# Schaltplan_Vier-Gewinnt_V3.net
KiCad netlist of a schematic drawn in EasyEDA
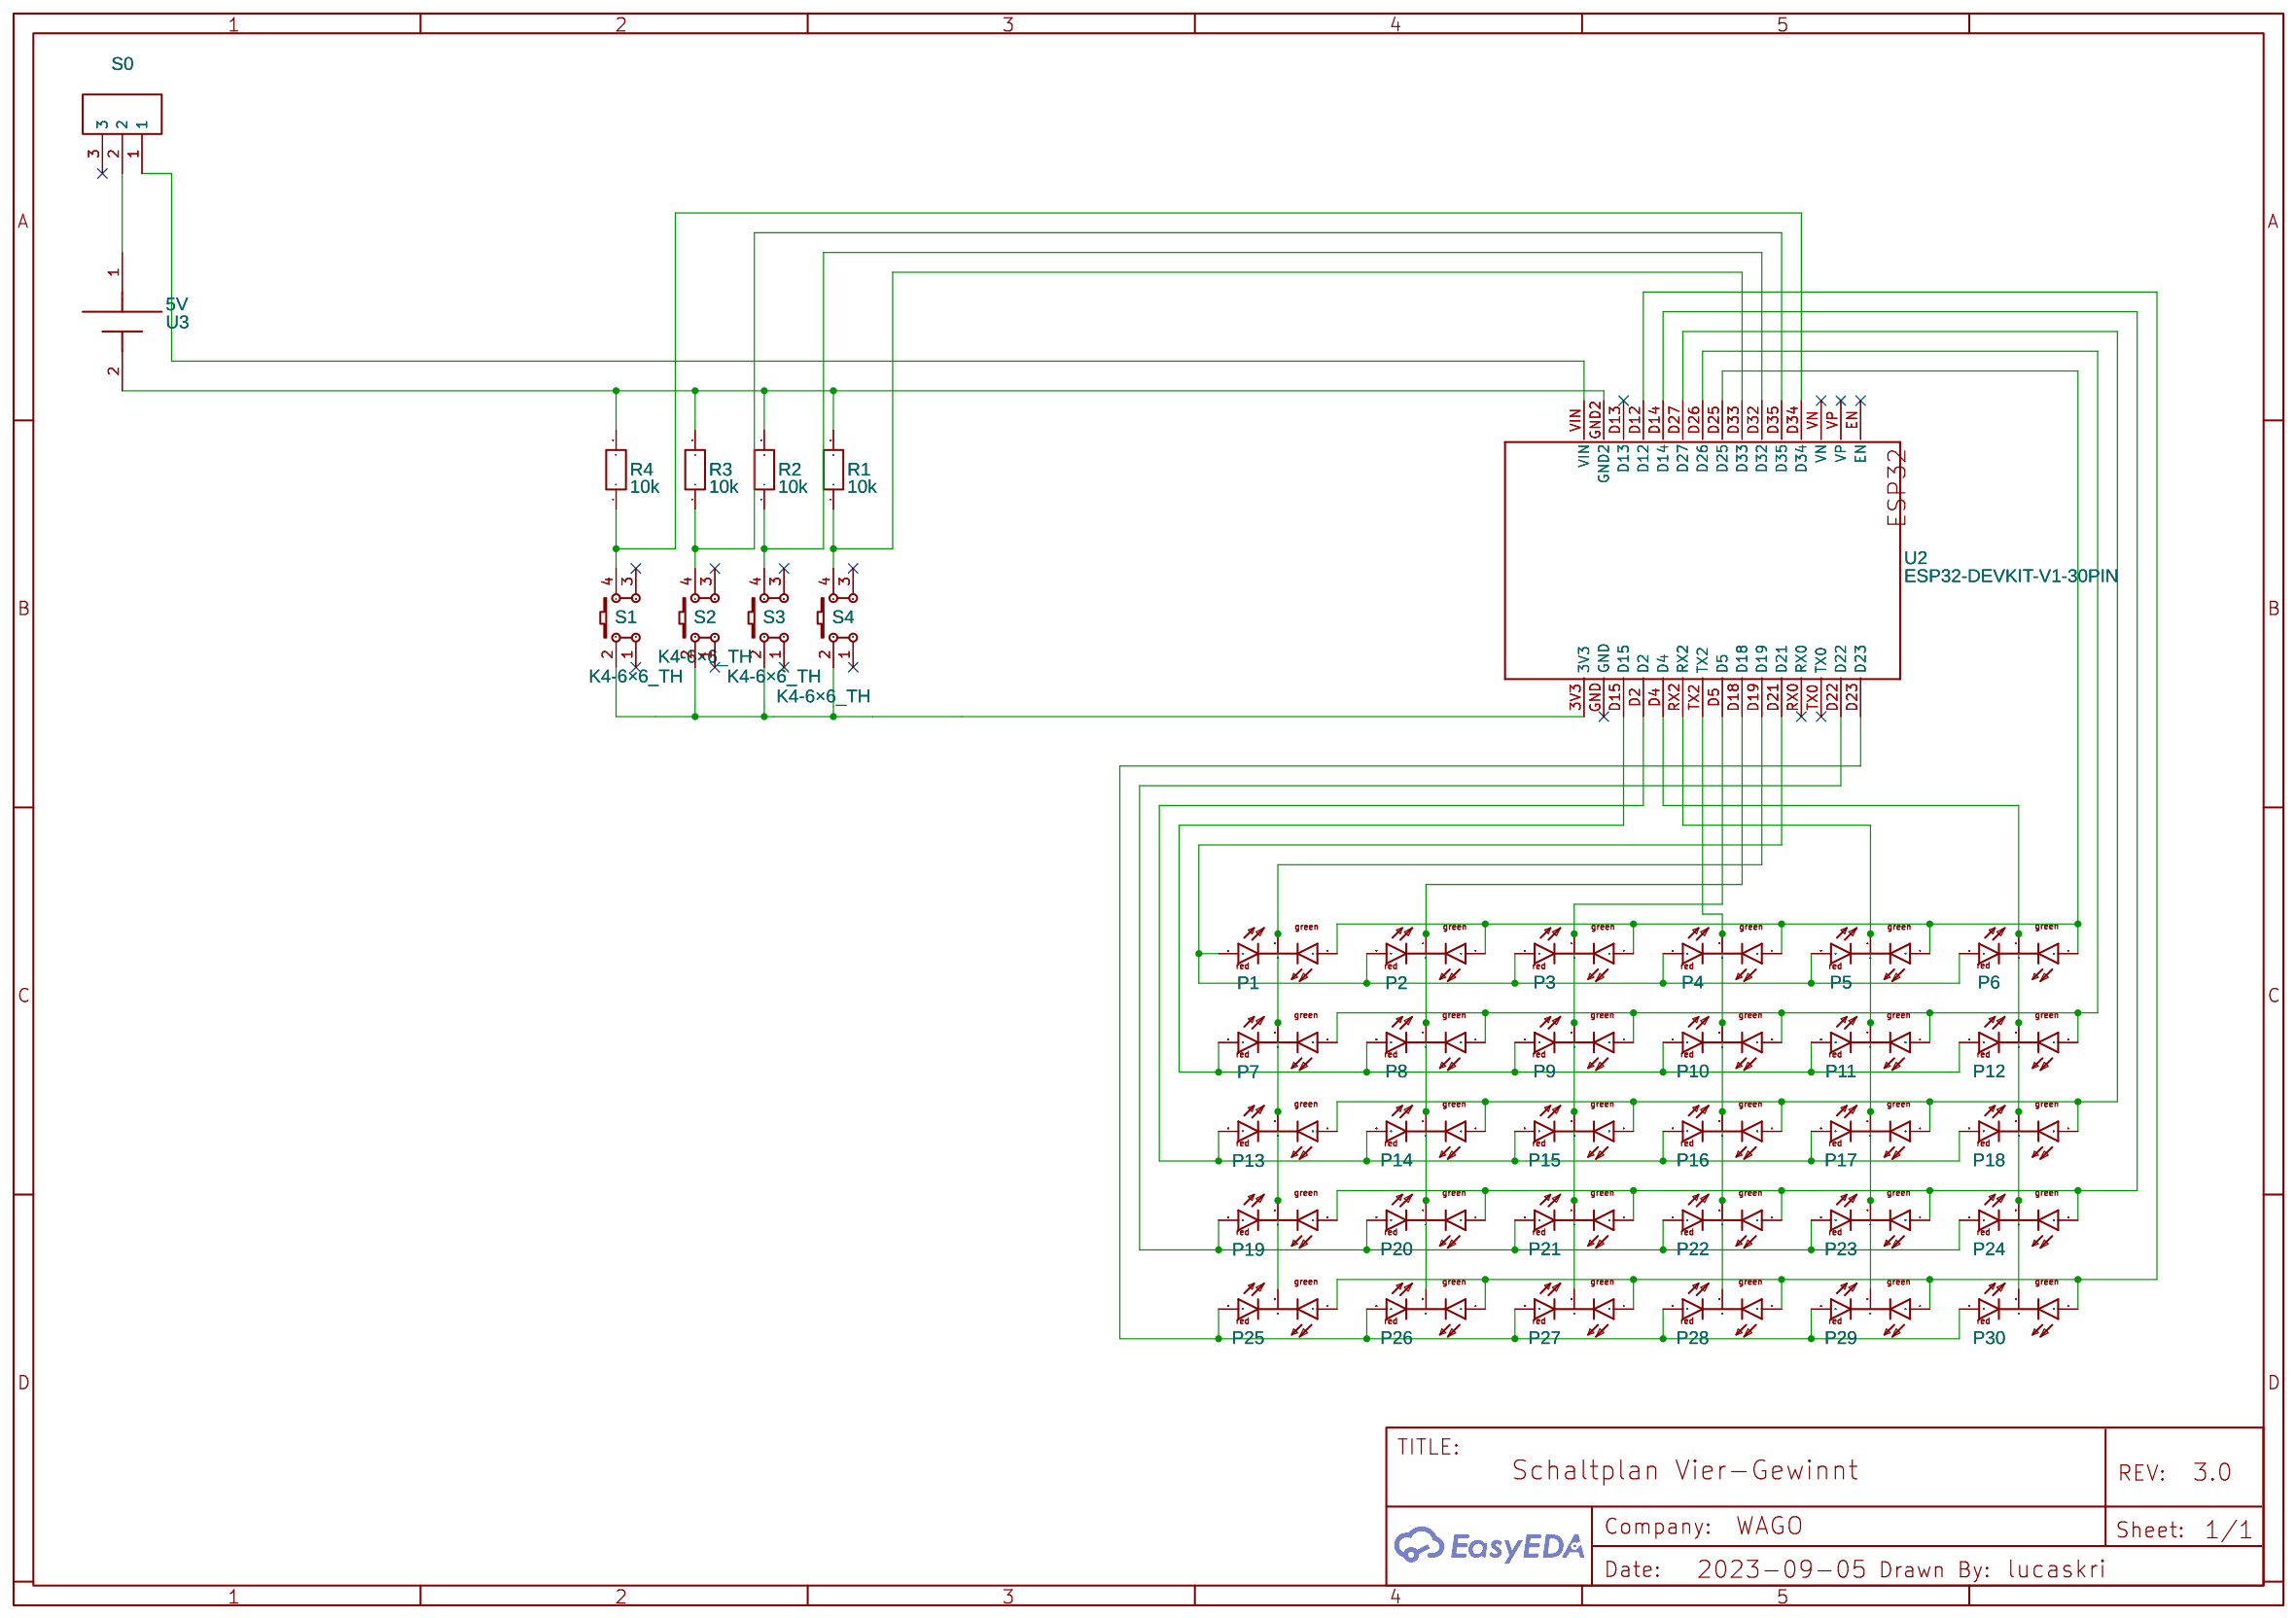
[diagram p0: schematic sheet]

(export (version "E")
  (design (tool "Eeschema 10.0.6"))
  (components
    (comp (ref "P1") (value "NO") (libsource (lib "") (part "DUOLED-RG-C_1")))
    (comp (ref "P2") (value "NO") (libsource (lib "") (part "DUOLED-RG-C_1")))
    (comp (ref "P3") (value "NO") (libsource (lib "") (part "DUOLED-RG-C_1")))
    (comp (ref "P4") (value "NO") (libsource (lib "") (part "DUOLED-RG-C_1")))
    (comp (ref "P5") (value "NO") (libsource (lib "") (part "DUOLED-RG-C_1")))
    (comp (ref "P6") (value "NO") (libsource (lib "") (part "DUOLED-RG-C")))
    (comp (ref "P7") (value "NO") (libsource (lib "") (part "DUOLED-RG-C")))
    (comp (ref "P8") (value "NO") (libsource (lib "") (part "DUOLED-RG-C")))
    (comp (ref "P9") (value "NO") (libsource (lib "") (part "DUOLED-RG-C")))
    (comp (ref "P10") (value "NO") (libsource (lib "") (part "DUOLED-RG-C")))
    (comp (ref "P11") (value "NO") (libsource (lib "") (part "DUOLED-RG-C")))
    (comp (ref "P12") (value "NO") (libsource (lib "") (part "DUOLED-RG-C")))
    (comp (ref "P13") (value "NO") (libsource (lib "") (part "DUOLED-RG-C")))
    (comp (ref "P14") (value "NO") (libsource (lib "") (part "DUOLED-RG-C")))
    (comp (ref "P15") (value "NO") (libsource (lib "") (part "DUOLED-RG-C")))
    (comp (ref "P16") (value "NO") (libsource (lib "") (part "DUOLED-RG-C")))
    (comp (ref "P17") (value "NO") (libsource (lib "") (part "DUOLED-RG-C")))
    (comp (ref "P18") (value "NO") (libsource (lib "") (part "DUOLED-RG-C")))
    (comp (ref "P19") (value "NO") (libsource (lib "") (part "DUOLED-RG-C")))
    (comp (ref "P20") (value "NO") (libsource (lib "") (part "DUOLED-RG-C")))
    (comp (ref "P21") (value "NO") (libsource (lib "") (part "DUOLED-RG-C")))
    (comp (ref "P22") (value "NO") (libsource (lib "") (part "DUOLED-RG-C")))
    (comp (ref "P23") (value "NO") (libsource (lib "") (part "DUOLED-RG-C")))
    (comp (ref "P24") (value "NO") (libsource (lib "") (part "DUOLED-RG-C")))
    (comp (ref "P25") (value "NO") (libsource (lib "") (part "DUOLED-RG-C")))
    (comp (ref "P26") (value "NO") (libsource (lib "") (part "DUOLED-RG-C")))
    (comp (ref "P27") (value "NO") (libsource (lib "") (part "DUOLED-RG-C")))
    (comp (ref "P28") (value "NO") (libsource (lib "") (part "DUOLED-RG-C")))
    (comp (ref "P29") (value "NO") (libsource (lib "") (part "DUOLED-RG-C")))
    (comp (ref "P30") (value "NO") (libsource (lib "") (part "DUOLED-RG-C")))
    (comp (ref "R1") (value "10k") (libsource (lib "") (part "R_AXIAL-0.3_EU")))
    (comp (ref "R2") (value "10k") (libsource (lib "") (part "R_AXIAL-0.3_EU")))
    (comp (ref "R3") (value "10k") (libsource (lib "") (part "R_AXIAL-0.3_EU")))
    (comp (ref "R4") (value "10k") (libsource (lib "") (part "R_AXIAL-0.3_EU")))
    (comp (ref "S0") (value "NO") (libsource (lib "") (part "CSS-1201")))
    (comp (ref "S1")
      (value "K4-6×6_TH")
      (fields (field (name "Manufacturer Part") "K2-1102DP-E4SW-04") (field (name "Manufacturer") "韩国韩荣"))
      (libsource (lib "") (part "K4-6×6_TH"))
    )
    (comp (ref "S2")
      (value "K4-6×6_TH")
      (fields (field (name "Manufacturer Part") "K2-1102DP-E4SW-04") (field (name "Manufacturer") "韩国韩荣"))
      (libsource (lib "") (part "K4-6×6_TH"))
    )
    (comp (ref "S3")
      (value "K4-6×6_TH")
      (fields (field (name "Manufacturer Part") "K2-1102DP-E4SW-04") (field (name "Manufacturer") "韩国韩荣"))
      (libsource (lib "") (part "K4-6×6_TH"))
    )
    (comp (ref "S4")
      (value "K4-6×6_TH")
      (fields (field (name "Manufacturer Part") "K2-1102DP-E4SW-04") (field (name "Manufacturer") "韩国韩荣"))
      (libsource (lib "") (part "K4-6×6_TH"))
    )
    (comp (ref "U2") (value "ESP32-DEVKIT-V1-30PIN") (libsource (lib "") (part "ESP32-DEVKIT-V1-30PIN")))
    (comp (ref "U3") (value "5V") (libsource (lib "") (part "Batterie")))
  )
  (nets
    (net (code "1") (name "Net-(P1-AG)") (class "Default")
      (node (ref "P1") (pin "AX") (pinfunction "AG_AX") (pintype "bidirectional"))
      (node (ref "P2") (pin "AX") (pinfunction "AG_AX") (pintype "bidirectional"))
      (node (ref "P3") (pin "AX") (pinfunction "AG_AX") (pintype "bidirectional"))
      (node (ref "P4") (pin "AX") (pinfunction "AG_AX") (pintype "bidirectional"))
      (node (ref "P5") (pin "AX") (pinfunction "AG_AX") (pintype "bidirectional"))
      (node (ref "P6") (pin "AX") (pinfunction "AG_AX") (pintype "bidirectional"))
      (node (ref "U2") (pin "D25") (pinfunction "D25_D25") (pintype "unspecified"))
    )
    (net (code "2") (name "Net-(P1-PadAR)") (class "Default")
      (node (ref "P1") (pin "AR") (pinfunction "AR_AR") (pintype "bidirectional"))
      (node (ref "P2") (pin "AR") (pinfunction "AR_AR") (pintype "bidirectional"))
      (node (ref "P3") (pin "AR") (pinfunction "AR_AR") (pintype "bidirectional"))
      (node (ref "P4") (pin "AR") (pinfunction "AR_AR") (pintype "bidirectional"))
      (node (ref "P5") (pin "AR") (pinfunction "AR_AR") (pintype "bidirectional"))
      (node (ref "P6") (pin "AR") (pinfunction "AR_AR") (pintype "bidirectional"))
      (node (ref "U2") (pin "D21") (pinfunction "D21_D21") (pintype "unspecified"))
    )
    (net (code "3") (name "Net-(P1-PadC)") (class "Default")
      (node (ref "P1") (pin "C") (pinfunction "C_C") (pintype "bidirectional"))
      (node (ref "P13") (pin "C") (pinfunction "C_C") (pintype "bidirectional"))
      (node (ref "P19") (pin "C") (pinfunction "C_C") (pintype "bidirectional"))
      (node (ref "P25") (pin "C") (pinfunction "C_C") (pintype "bidirectional"))
      (node (ref "P7") (pin "C") (pinfunction "C_C") (pintype "bidirectional"))
      (node (ref "U2") (pin "D19") (pinfunction "D19_D19") (pintype "unspecified"))
    )
    (net (code "4") (name "Net-(P10-AG)") (class "Default")
      (node (ref "P10") (pin "AX") (pinfunction "AG_AX") (pintype "bidirectional"))
      (node (ref "P11") (pin "AX") (pinfunction "AG_AX") (pintype "bidirectional"))
      (node (ref "P12") (pin "AX") (pinfunction "AG_AX") (pintype "bidirectional"))
      (node (ref "P7") (pin "AX") (pinfunction "AG_AX") (pintype "bidirectional"))
      (node (ref "P8") (pin "AX") (pinfunction "AG_AX") (pintype "bidirectional"))
      (node (ref "P9") (pin "AX") (pinfunction "AG_AX") (pintype "bidirectional"))
      (node (ref "U2") (pin "D26") (pinfunction "D26_D26") (pintype "unspecified"))
    )
    (net (code "5") (name "Net-(P10-PadAR)") (class "Default")
      (node (ref "P10") (pin "AR") (pinfunction "AR_AR") (pintype "bidirectional"))
      (node (ref "P11") (pin "AR") (pinfunction "AR_AR") (pintype "bidirectional"))
      (node (ref "P12") (pin "AR") (pinfunction "AR_AR") (pintype "bidirectional"))
      (node (ref "P7") (pin "AR") (pinfunction "AR_AR") (pintype "bidirectional"))
      (node (ref "P8") (pin "AR") (pinfunction "AR_AR") (pintype "bidirectional"))
      (node (ref "P9") (pin "AR") (pinfunction "AR_AR") (pintype "bidirectional"))
      (node (ref "U2") (pin "D15") (pinfunction "D15_D15") (pintype "unspecified"))
    )
    (net (code "6") (name "Net-(P10-PadC)") (class "Default")
      (node (ref "P10") (pin "C") (pinfunction "C_C") (pintype "bidirectional"))
      (node (ref "P16") (pin "C") (pinfunction "C_C") (pintype "bidirectional"))
      (node (ref "P22") (pin "C") (pinfunction "C_C") (pintype "bidirectional"))
      (node (ref "P28") (pin "C") (pinfunction "C_C") (pintype "bidirectional"))
      (node (ref "P4") (pin "C") (pinfunction "C_C") (pintype "bidirectional"))
      (node (ref "U2") (pin "TX2") (pinfunction "TX2_TX2") (pintype "unspecified"))
    )
    (net (code "7") (name "Net-(P11-PadC)") (class "Default")
      (node (ref "P11") (pin "C") (pinfunction "C_C") (pintype "bidirectional"))
      (node (ref "P17") (pin "C") (pinfunction "C_C") (pintype "bidirectional"))
      (node (ref "P23") (pin "C") (pinfunction "C_C") (pintype "bidirectional"))
      (node (ref "P29") (pin "C") (pinfunction "C_C") (pintype "bidirectional"))
      (node (ref "P5") (pin "C") (pinfunction "C_C") (pintype "bidirectional"))
      (node (ref "U2") (pin "RX2") (pinfunction "RX2_RX2") (pintype "unspecified"))
    )
    (net (code "8") (name "Net-(P12-PadC)") (class "Default")
      (node (ref "P12") (pin "C") (pinfunction "C_C") (pintype "bidirectional"))
      (node (ref "P18") (pin "C") (pinfunction "C_C") (pintype "bidirectional"))
      (node (ref "P24") (pin "C") (pinfunction "C_C") (pintype "bidirectional"))
      (node (ref "P30") (pin "C") (pinfunction "C_C") (pintype "bidirectional"))
      (node (ref "P6") (pin "C") (pinfunction "C_C") (pintype "bidirectional"))
      (node (ref "U2") (pin "D4") (pinfunction "D4_D4") (pintype "unspecified"))
    )
    (net (code "9") (name "Net-(P13-AG)") (class "Default")
      (node (ref "P13") (pin "AX") (pinfunction "AG_AX") (pintype "bidirectional"))
      (node (ref "P14") (pin "AX") (pinfunction "AG_AX") (pintype "bidirectional"))
      (node (ref "P15") (pin "AX") (pinfunction "AG_AX") (pintype "bidirectional"))
      (node (ref "P16") (pin "AX") (pinfunction "AG_AX") (pintype "bidirectional"))
      (node (ref "P17") (pin "AX") (pinfunction "AG_AX") (pintype "bidirectional"))
      (node (ref "P18") (pin "AX") (pinfunction "AG_AX") (pintype "bidirectional"))
      (node (ref "U2") (pin "D27") (pinfunction "D27_D27") (pintype "unspecified"))
    )
    (net (code "10") (name "Net-(P13-PadAR)") (class "Default")
      (node (ref "P13") (pin "AR") (pinfunction "AR_AR") (pintype "bidirectional"))
      (node (ref "P14") (pin "AR") (pinfunction "AR_AR") (pintype "bidirectional"))
      (node (ref "P15") (pin "AR") (pinfunction "AR_AR") (pintype "bidirectional"))
      (node (ref "P16") (pin "AR") (pinfunction "AR_AR") (pintype "bidirectional"))
      (node (ref "P17") (pin "AR") (pinfunction "AR_AR") (pintype "bidirectional"))
      (node (ref "P18") (pin "AR") (pinfunction "AR_AR") (pintype "bidirectional"))
      (node (ref "U2") (pin "D2") (pinfunction "D2_D2") (pintype "unspecified"))
    )
    (net (code "11") (name "Net-(P14-PadC)") (class "Default")
      (node (ref "P14") (pin "C") (pinfunction "C_C") (pintype "bidirectional"))
      (node (ref "P2") (pin "C") (pinfunction "C_C") (pintype "bidirectional"))
      (node (ref "P20") (pin "C") (pinfunction "C_C") (pintype "bidirectional"))
      (node (ref "P26") (pin "C") (pinfunction "C_C") (pintype "bidirectional"))
      (node (ref "P8") (pin "C") (pinfunction "C_C") (pintype "bidirectional"))
      (node (ref "U2") (pin "D18") (pinfunction "D18_D18") (pintype "unspecified"))
    )
    (net (code "12") (name "Net-(P15-PadC)") (class "Default")
      (node (ref "P15") (pin "C") (pinfunction "C_C") (pintype "bidirectional"))
      (node (ref "P21") (pin "C") (pinfunction "C_C") (pintype "bidirectional"))
      (node (ref "P27") (pin "C") (pinfunction "C_C") (pintype "bidirectional"))
      (node (ref "P3") (pin "C") (pinfunction "C_C") (pintype "bidirectional"))
      (node (ref "P9") (pin "C") (pinfunction "C_C") (pintype "bidirectional"))
      (node (ref "U2") (pin "D5") (pinfunction "D5_D5") (pintype "unspecified"))
    )
    (net (code "13") (name "Net-(P19-AG)") (class "Default")
      (node (ref "P19") (pin "AX") (pinfunction "AG_AX") (pintype "bidirectional"))
      (node (ref "P20") (pin "AX") (pinfunction "AG_AX") (pintype "bidirectional"))
      (node (ref "P21") (pin "AX") (pinfunction "AG_AX") (pintype "bidirectional"))
      (node (ref "P22") (pin "AX") (pinfunction "AG_AX") (pintype "bidirectional"))
      (node (ref "P23") (pin "AX") (pinfunction "AG_AX") (pintype "bidirectional"))
      (node (ref "P24") (pin "AX") (pinfunction "AG_AX") (pintype "bidirectional"))
      (node (ref "U2") (pin "D14") (pinfunction "D14_D14") (pintype "unspecified"))
    )
    (net (code "14") (name "Net-(P19-PadAR)") (class "Default")
      (node (ref "P19") (pin "AR") (pinfunction "AR_AR") (pintype "bidirectional"))
      (node (ref "P20") (pin "AR") (pinfunction "AR_AR") (pintype "bidirectional"))
      (node (ref "P21") (pin "AR") (pinfunction "AR_AR") (pintype "bidirectional"))
      (node (ref "P22") (pin "AR") (pinfunction "AR_AR") (pintype "bidirectional"))
      (node (ref "P23") (pin "AR") (pinfunction "AR_AR") (pintype "bidirectional"))
      (node (ref "P24") (pin "AR") (pinfunction "AR_AR") (pintype "bidirectional"))
      (node (ref "U2") (pin "D22") (pinfunction "D22_D22") (pintype "unspecified"))
    )
    (net (code "15") (name "Net-(P25-AG)") (class "Default")
      (node (ref "P25") (pin "AX") (pinfunction "AG_AX") (pintype "bidirectional"))
      (node (ref "P26") (pin "AX") (pinfunction "AG_AX") (pintype "bidirectional"))
      (node (ref "P27") (pin "AX") (pinfunction "AG_AX") (pintype "bidirectional"))
      (node (ref "P28") (pin "AX") (pinfunction "AG_AX") (pintype "bidirectional"))
      (node (ref "P29") (pin "AX") (pinfunction "AG_AX") (pintype "bidirectional"))
      (node (ref "P30") (pin "AX") (pinfunction "AG_AX") (pintype "bidirectional"))
      (node (ref "U2") (pin "D12") (pinfunction "D12_D12") (pintype "unspecified"))
    )
    (net (code "16") (name "Net-(P25-PadAR)") (class "Default")
      (node (ref "P25") (pin "AR") (pinfunction "AR_AR") (pintype "bidirectional"))
      (node (ref "P26") (pin "AR") (pinfunction "AR_AR") (pintype "bidirectional"))
      (node (ref "P27") (pin "AR") (pinfunction "AR_AR") (pintype "bidirectional"))
      (node (ref "P28") (pin "AR") (pinfunction "AR_AR") (pintype "bidirectional"))
      (node (ref "P29") (pin "AR") (pinfunction "AR_AR") (pintype "bidirectional"))
      (node (ref "P30") (pin "AR") (pinfunction "AR_AR") (pintype "bidirectional"))
      (node (ref "U2") (pin "D23") (pinfunction "D23_D23") (pintype "unspecified"))
    )
    (net (code "17") (name "Net-(R1-Pad1)") (class "Default")
      (node (ref "R1") (pin "1") (pinfunction "1_1") (pintype "unspecified"))
      (node (ref "S4") (pin "4") (pinfunction "4_4") (pintype "unspecified"))
      (node (ref "U2") (pin "D33") (pinfunction "D33_D33") (pintype "unspecified"))
    )
    (net (code "18") (name "Net-(R2-Pad1)") (class "Default")
      (node (ref "R2") (pin "1") (pinfunction "1_1") (pintype "unspecified"))
      (node (ref "S3") (pin "4") (pinfunction "4_4") (pintype "unspecified"))
      (node (ref "U2") (pin "D32") (pinfunction "D32_D32") (pintype "unspecified"))
    )
    (net (code "19") (name "Net-(R3-Pad1)") (class "Default")
      (node (ref "R3") (pin "1") (pinfunction "1_1") (pintype "unspecified"))
      (node (ref "S2") (pin "4") (pinfunction "4_4") (pintype "unspecified"))
      (node (ref "U2") (pin "D35") (pinfunction "D35_D35") (pintype "unspecified"))
    )
    (net (code "20") (name "Net-(R4-Pad1)") (class "Default")
      (node (ref "R4") (pin "1") (pinfunction "1_1") (pintype "unspecified"))
      (node (ref "S1") (pin "4") (pinfunction "4_4") (pintype "unspecified"))
      (node (ref "U2") (pin "D34") (pinfunction "D34_D34") (pintype "unspecified"))
    )
    (net (code "21") (name "Net-(S0-Pad1)") (class "Default")
      (node (ref "S0") (pin "1") (pinfunction "1_1") (pintype "unspecified"))
      (node (ref "U2") (pin "VIN") (pinfunction "VIN_VIN") (pintype "unspecified"))
    )
    (net (code "22") (name "Net-(S1-Pad2)") (class "Default")
      (node (ref "S1") (pin "2") (pinfunction "2_2") (pintype "unspecified"))
      (node (ref "S2") (pin "2") (pinfunction "2_2") (pintype "unspecified"))
      (node (ref "S3") (pin "2") (pinfunction "2_2") (pintype "unspecified"))
      (node (ref "S4") (pin "2") (pinfunction "2_2") (pintype "unspecified"))
      (node (ref "U2") (pin "3V3") (pinfunction "3V3_3V3") (pintype "unspecified"))
    )
    (net (code "23") (name "Net-(U3-+)") (class "Default")
      (node (ref "S0") (pin "2") (pinfunction "2_2") (pintype "unspecified"))
      (node (ref "U3") (pin "1") (pinfunction "+_1") (pintype "unspecified"))
    )
    (net (code "24") (name "Net-(U3--)") (class "Default")
      (node (ref "R1") (pin "2") (pinfunction "2_2") (pintype "unspecified"))
      (node (ref "R2") (pin "2") (pinfunction "2_2") (pintype "unspecified"))
      (node (ref "R3") (pin "2") (pinfunction "2_2") (pintype "unspecified"))
      (node (ref "R4") (pin "2") (pinfunction "2_2") (pintype "unspecified"))
      (node (ref "U2") (pin "GND2") (pinfunction "GND2_GND2") (pintype "unspecified"))
      (node (ref "U3") (pin "2") (pinfunction "-_2") (pintype "unspecified"))
    )
    (net (code "25") (name "unconnected-(S0-Pad3)") (class "Default")
      (node (ref "S0") (pin "3") (pinfunction "3_3") (pintype "unspecified+no_connect"))
    )
    (net (code "26") (name "unconnected-(S1-Pad1)") (class "Default")
      (node (ref "S1") (pin "1") (pinfunction "1_1") (pintype "unspecified+no_connect"))
    )
    (net (code "27") (name "unconnected-(S1-Pad3)") (class "Default")
      (node (ref "S1") (pin "3") (pinfunction "3_3") (pintype "unspecified+no_connect"))
    )
    (net (code "28") (name "unconnected-(S2-Pad1)") (class "Default")
      (node (ref "S2") (pin "1") (pinfunction "1_1") (pintype "unspecified+no_connect"))
    )
    (net (code "29") (name "unconnected-(S2-Pad3)") (class "Default")
      (node (ref "S2") (pin "3") (pinfunction "3_3") (pintype "unspecified+no_connect"))
    )
    (net (code "30") (name "unconnected-(S3-Pad1)") (class "Default")
      (node (ref "S3") (pin "1") (pinfunction "1_1") (pintype "unspecified+no_connect"))
    )
    (net (code "31") (name "unconnected-(S3-Pad3)") (class "Default")
      (node (ref "S3") (pin "3") (pinfunction "3_3") (pintype "unspecified+no_connect"))
    )
    (net (code "32") (name "unconnected-(S4-Pad1)") (class "Default")
      (node (ref "S4") (pin "1") (pinfunction "1_1") (pintype "unspecified+no_connect"))
    )
    (net (code "33") (name "unconnected-(S4-Pad3)") (class "Default")
      (node (ref "S4") (pin "3") (pinfunction "3_3") (pintype "unspecified+no_connect"))
    )
    (net (code "34") (name "unconnected-(U2-PadD13)") (class "Default")
      (node (ref "U2") (pin "D13") (pinfunction "D13_D13") (pintype "unspecified+no_connect"))
    )
    (net (code "35") (name "unconnected-(U2-PadEN)") (class "Default")
      (node (ref "U2") (pin "EN") (pinfunction "EN_EN") (pintype "unspecified+no_connect"))
    )
    (net (code "36") (name "unconnected-(U2-PadGND)") (class "Default")
      (node (ref "U2") (pin "GND") (pinfunction "GND_GND") (pintype "unspecified+no_connect"))
    )
    (net (code "37") (name "unconnected-(U2-PadRX0)") (class "Default")
      (node (ref "U2") (pin "RX0") (pinfunction "RX0_RX0") (pintype "unspecified+no_connect"))
    )
    (net (code "38") (name "unconnected-(U2-PadTX0)") (class "Default")
      (node (ref "U2") (pin "TX0") (pinfunction "TX0_TX0") (pintype "unspecified+no_connect"))
    )
    (net (code "39") (name "unconnected-(U2-PadVN)") (class "Default")
      (node (ref "U2") (pin "VN") (pinfunction "VN_VN") (pintype "unspecified+no_connect"))
    )
    (net (code "40") (name "unconnected-(U2-PadVP)") (class "Default")
      (node (ref "U2") (pin "VP") (pinfunction "VP_VP") (pintype "unspecified+no_connect"))
    )
  )
)
